# main.net
KiCad netlist of a schematic drawn in Altium Designer
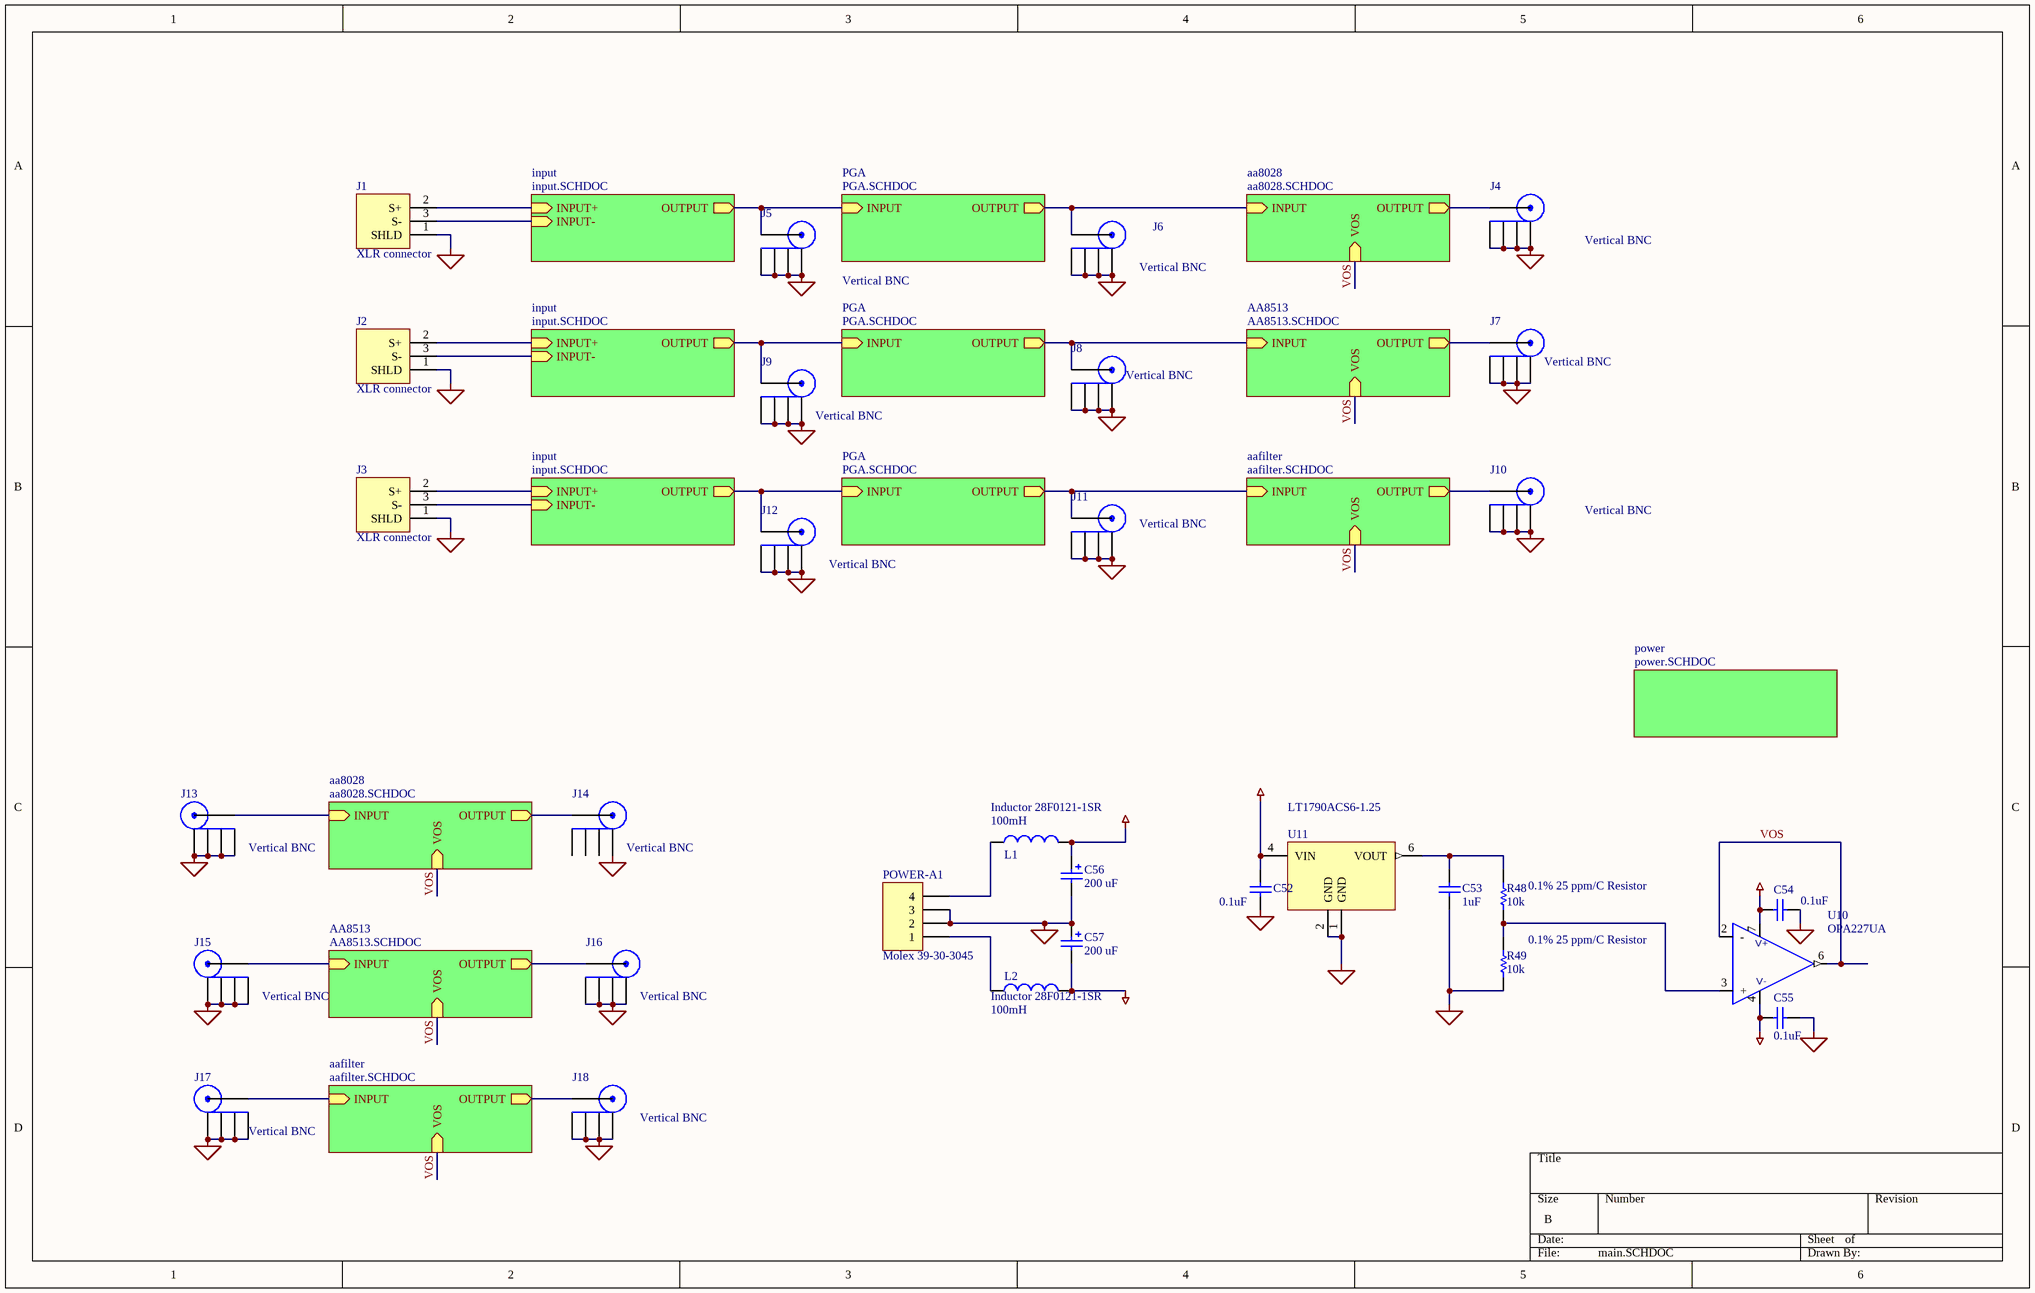
[diagram p0: main.SCHDOC]

(export (version "E")
  (design (tool "Eeschema 10.0.6"))
  (components
    (comp (ref "C52")
      (value "Cap")
      (footprint "CC1608-0603")
      (description "Capacitor")
      (fields
        (field (name "MANUFACTURER") "Generic Components")
        (field (name "ALTIUM_VALUE") "0.1uF")
        (field (name "PUBLISHER") "Altium Limited")
      )
      (libsource (lib "Miscellaneous Devices") (part "Cap"))
    )
    (comp (ref "C53")
      (value "Cap")
      (footprint "CC1608-0603")
      (description "Capacitor")
      (fields
        (field (name "MANUFACTURER") "Generic Components")
        (field (name "ALTIUM_VALUE") "1uF")
        (field (name "PUBLISHER") "Altium Limited")
      )
      (libsource (lib "Miscellaneous Devices") (part "Cap"))
    )
    (comp (ref "C54")
      (value "Cap")
      (footprint "CC1608-0603")
      (description "Capacitor")
      (fields
        (field (name "MANUFACTURER") "Generic Components")
        (field (name "ALTIUM_VALUE") "0.1uF")
        (field (name "PUBLISHER") "Altium Limited")
      )
      (libsource (lib "Miscellaneous Devices") (part "Cap"))
    )
    (comp (ref "C55")
      (value "Cap")
      (footprint "CC1608-0603")
      (description "Capacitor")
      (fields
        (field (name "MANUFACTURER") "Generic Components")
        (field (name "ALTIUM_VALUE") "0.1uF")
        (field (name "PUBLISHER") "Altium Limited")
      )
      (libsource (lib "Miscellaneous Devices") (part "Cap"))
    )
    (comp (ref "C56")
      (value "200 uF")
      (footprint "PanasonicE")
      (description "Polarized Capacitor (Surface Mount)")
      (fields (field (name "MANUFACTURER") "Generic Components") (field (name "PUBLISHER") "Altium Limited"))
      (libsource (lib "Miscellaneous Devices") (part "Cap Pol3"))
    )
    (comp (ref "C57")
      (value "200 uF")
      (footprint "PanasonicE")
      (description "Polarized Capacitor (Surface Mount)")
      (fields (field (name "MANUFACTURER") "Generic Components") (field (name "PUBLISHER") "Altium Limited"))
      (libsource (lib "Miscellaneous Devices") (part "Cap Pol3"))
    )
    (comp (ref "J1")
      (value "XLR connector")
      (footprint "NC3FAH-0")
      (description "XLR balanced connector, standard")
      (libsource (lib "My devices") (part "XLR"))
    )
    (comp (ref "J2")
      (value "XLR connector")
      (footprint "NC3FAH-0")
      (description "XLR balanced connector, standard")
      (libsource (lib "My devices") (part "XLR"))
    )
    (comp (ref "J3")
      (value "XLR connector")
      (footprint "NC3FAH-0")
      (description "XLR balanced connector, standard")
      (libsource (lib "My devices") (part "XLR"))
    )
    (comp (ref "J4")
      (value "Vertical BNC")
      (footprint "Vertical BNC 227699-1")
      (description "Vertical BNC with correct grounding pin behavior")
      (libsource (lib "My devices") (part "VERTBNC"))
    )
    (comp (ref "J5")
      (value "Vertical BNC")
      (footprint "Vertical BNC 227699-1")
      (description "Vertical BNC with correct grounding pin behavior")
      (libsource (lib "My devices") (part "VERTBNC"))
    )
    (comp (ref "J6")
      (value "Vertical BNC")
      (footprint "Vertical BNC 227699-1")
      (description "Vertical BNC with correct grounding pin behavior")
      (libsource (lib "My devices") (part "VERTBNC"))
    )
    (comp (ref "J7")
      (value "Vertical BNC")
      (footprint "Vertical BNC 227699-1")
      (description "Vertical BNC with correct grounding pin behavior")
      (libsource (lib "My devices") (part "VERTBNC"))
    )
    (comp (ref "J8")
      (value "Vertical BNC")
      (footprint "Vertical BNC 227699-1")
      (description "Vertical BNC with correct grounding pin behavior")
      (libsource (lib "My devices") (part "VERTBNC"))
    )
    (comp (ref "J9")
      (value "Vertical BNC")
      (footprint "Vertical BNC 227699-1")
      (description "Vertical BNC with correct grounding pin behavior")
      (libsource (lib "My devices") (part "VERTBNC"))
    )
    (comp (ref "J10")
      (value "Vertical BNC")
      (footprint "Vertical BNC 227699-1")
      (description "Vertical BNC with correct grounding pin behavior")
      (libsource (lib "My devices") (part "VERTBNC"))
    )
    (comp (ref "J11")
      (value "Vertical BNC")
      (footprint "Vertical BNC 227699-1")
      (description "Vertical BNC with correct grounding pin behavior")
      (libsource (lib "My devices") (part "VERTBNC"))
    )
    (comp (ref "J12")
      (value "Vertical BNC")
      (footprint "Vertical BNC 227699-1")
      (description "Vertical BNC with correct grounding pin behavior")
      (libsource (lib "My devices") (part "VERTBNC"))
    )
    (comp (ref "J13")
      (value "Vertical BNC")
      (footprint "Vertical BNC 227699-1")
      (description "Vertical BNC with correct grounding pin behavior")
      (libsource (lib "My devices") (part "VERTBNC"))
    )
    (comp (ref "J14")
      (value "Vertical BNC")
      (footprint "Vertical BNC 227699-1")
      (description "Vertical BNC with correct grounding pin behavior")
      (libsource (lib "My devices") (part "VERTBNC"))
    )
    (comp (ref "J15")
      (value "Vertical BNC")
      (footprint "Vertical BNC 227699-1")
      (description "Vertical BNC with correct grounding pin behavior")
      (libsource (lib "My devices") (part "VERTBNC"))
    )
    (comp (ref "J16")
      (value "Vertical BNC")
      (footprint "Vertical BNC 227699-1")
      (description "Vertical BNC with correct grounding pin behavior")
      (libsource (lib "My devices") (part "VERTBNC"))
    )
    (comp (ref "J17")
      (value "Vertical BNC")
      (footprint "Vertical BNC 227699-1")
      (description "Vertical BNC with correct grounding pin behavior")
      (libsource (lib "My devices") (part "VERTBNC"))
    )
    (comp (ref "J18")
      (value "Vertical BNC")
      (footprint "Vertical BNC 227699-1")
      (description "Vertical BNC with correct grounding pin behavior")
      (libsource (lib "My devices") (part "VERTBNC"))
    )
    (comp (ref "L1")
      (value "Inductor 28F0121-1SR")
      (footprint "STEWARD_1SR")
      (description "Inductor")
      (fields
        (field (name "MANUFACTURER") "Generic Components")
        (field (name "ALTIUM_VALUE") "100mH")
        (field (name "PUBLISHER") "Altium Limited")
      )
      (libsource (lib "Miscellaneous Devices") (part "Inductor"))
    )
    (comp (ref "L2")
      (value "Inductor 28F0121-1SR")
      (footprint "STEWARD_1SR")
      (description "Inductor")
      (fields
        (field (name "MANUFACTURER") "Generic Components")
        (field (name "ALTIUM_VALUE") "100mH")
        (field (name "PUBLISHER") "Altium Limited")
      )
      (libsource (lib "Miscellaneous Devices") (part "Inductor"))
    )
    (comp (ref "POWER-A1")
      (value "Molex 39-30-3045")
      (footprint "MJ4RTHR")
      (description "Header, 4-Pin")
      (fields (field (name "MANUFACTURER") "Generic Components") (field (name "PUBLISHER") "Altium Limited"))
      (libsource (lib "Miscellaneous Connectors") (part "Header 4"))
    )
    (comp (ref "R48")
      (value "0.1% 25 ppm/C Resistor")
      (footprint "C3216-1206")
      (description "Resistor")
      (fields
        (field (name "MANUFACTURER") "Generic Components")
        (field (name "ALTIUM_VALUE") "10k")
        (field (name "PUBLISHER") "Altium Limited")
      )
      (libsource (lib "Miscellaneous Devices") (part "Res1"))
    )
    (comp (ref "R49")
      (value "0.1% 25 ppm/C Resistor")
      (footprint "C3216-1206")
      (description "Resistor")
      (fields
        (field (name "MANUFACTURER") "Generic Components")
        (field (name "ALTIUM_VALUE") "10k")
        (field (name "PUBLISHER") "Altium Limited")
      )
      (libsource (lib "Miscellaneous Devices") (part "Res1"))
    )
    (comp (ref "U10")
      (value "OPA227UA")
      (footprint "SO-G8/D5.1")
      (libsource (lib "My devices") (part "OPA227UA"))
    )
    (comp (ref "U11")
      (value "LT1790ACS6-1.25")
      (footprint "LTI SOT-23 ThinSOT")
      (libsource (lib "My devices") (part "LT1790"))
    )
  )
  (nets
    (net (code "1") (name "/INPUT") (class "Default")
      (node (ref "J17") (pin "1") (pinfunction "PIN_1") (pintype "passive"))
    )
    (net (code "2") (name "/INPUT+") (class "Default")
      (node (ref "J3") (pin "2") (pinfunction "S+_2") (pintype "passive"))
    )
    (net (code "3") (name "/INPUT+_1") (class "Default")
      (node (ref "J1") (pin "2") (pinfunction "S+_2") (pintype "passive"))
    )
    (net (code "4") (name "/INPUT+_2") (class "Default")
      (node (ref "J2") (pin "2") (pinfunction "S+_2") (pintype "passive"))
    )
    (net (code "5") (name "/INPUT-") (class "Default")
      (node (ref "J2") (pin "3") (pinfunction "S-_3") (pintype "passive"))
    )
    (net (code "6") (name "/INPUT-_1") (class "Default")
      (node (ref "J1") (pin "3") (pinfunction "S-_3") (pintype "passive"))
    )
    (net (code "7") (name "/INPUT-_2") (class "Default")
      (node (ref "J3") (pin "3") (pinfunction "S-_3") (pintype "passive"))
    )
    (net (code "8") (name "/INPUT_1") (class "Default")
      (node (ref "J15") (pin "1") (pinfunction "PIN_1") (pintype "passive"))
    )
    (net (code "9") (name "/INPUT_2") (class "Default")
      (node (ref "J13") (pin "1") (pinfunction "PIN_1") (pintype "passive"))
    )
    (net (code "10") (name "/OUTPUT") (class "Default")
      (node (ref "J7") (pin "1") (pinfunction "PIN_1") (pintype "passive"))
    )
    (net (code "11") (name "/OUTPUT_1") (class "Default")
      (node (ref "J18") (pin "1") (pinfunction "PIN_1") (pintype "passive"))
    )
    (net (code "12") (name "/OUTPUT_2") (class "Default")
      (node (ref "J14") (pin "1") (pinfunction "PIN_1") (pintype "passive"))
    )
    (net (code "13") (name "/OUTPUT_3") (class "Default")
      (node (ref "J16") (pin "1") (pinfunction "PIN_1") (pintype "passive"))
    )
    (net (code "14") (name "/OUTPUT_4") (class "Default")
      (node (ref "J5") (pin "1") (pinfunction "PIN_1") (pintype "passive"))
    )
    (net (code "15") (name "/OUTPUT_5") (class "Default")
      (node (ref "J9") (pin "1") (pinfunction "PIN_1") (pintype "passive"))
    )
    (net (code "16") (name "/OUTPUT_6") (class "Default")
      (node (ref "J12") (pin "1") (pinfunction "PIN_1") (pintype "passive"))
    )
    (net (code "17") (name "/OUTPUT_7") (class "Default")
      (node (ref "J6") (pin "1") (pinfunction "PIN_1") (pintype "passive"))
    )
    (net (code "18") (name "/OUTPUT_8") (class "Default")
      (node (ref "J11") (pin "1") (pinfunction "PIN_1") (pintype "passive"))
    )
    (net (code "19") (name "/OUTPUT_9") (class "Default")
      (node (ref "J8") (pin "1") (pinfunction "PIN_1") (pintype "passive"))
    )
    (net (code "20") (name "/OUTPUT_10") (class "Default")
      (node (ref "J10") (pin "1") (pinfunction "PIN_1") (pintype "passive"))
    )
    (net (code "21") (name "/OUTPUT_11") (class "Default")
      (node (ref "J4") (pin "1") (pinfunction "PIN_1") (pintype "passive"))
    )
    (net (code "22") (name "/VOS") (class "Default")
      (node (ref "U10") (pin "2") (pinfunction "-_2") (pintype "passive"))
      (node (ref "U10") (pin "6") (pinfunction "Vout_6") (pintype "output"))
    )
    (net (code "23") (name "AVDD") (class "Default")
      (node (ref "C52") (pin "1") (pinfunction "1_1") (pintype "passive"))
      (node (ref "C54") (pin "2") (pinfunction "2_2") (pintype "passive"))
      (node (ref "C56") (pin "1") (pinfunction "1_1") (pintype "passive"))
      (node (ref "L1") (pin "2") (pinfunction "2_2") (pintype "passive"))
      (node (ref "U10") (pin "7") (pinfunction "V+_7") (pintype "power_in"))
      (node (ref "U11") (pin "4") (pinfunction "VIN_4") (pintype "power_in"))
    )
    (net (code "24") (name "AVSS") (class "Default")
      (node (ref "C55") (pin "2") (pinfunction "2_2") (pintype "passive"))
      (node (ref "C57") (pin "2") (pinfunction "2_2") (pintype "passive"))
      (node (ref "L2") (pin "2") (pinfunction "2_2") (pintype "passive"))
      (node (ref "U10") (pin "4") (pinfunction "V-_4") (pintype "power_in"))
    )
    (net (code "25") (name "GND") (class "Default")
      (node (ref "C52") (pin "2") (pinfunction "2_2") (pintype "passive"))
      (node (ref "C53") (pin "2") (pinfunction "2_2") (pintype "passive"))
      (node (ref "C54") (pin "1") (pinfunction "1_1") (pintype "passive"))
      (node (ref "C55") (pin "1") (pinfunction "1_1") (pintype "passive"))
      (node (ref "C56") (pin "2") (pinfunction "2_2") (pintype "passive"))
      (node (ref "C57") (pin "1") (pinfunction "1_1") (pintype "passive"))
      (node (ref "J1") (pin "1") (pinfunction "SHLD_1") (pintype "passive"))
      (node (ref "J10") (pin "2") (pinfunction "SHLD_2") (pintype "passive"))
      (node (ref "J10") (pin "3") (pinfunction "SHLD_3") (pintype "passive"))
      (node (ref "J10") (pin "4") (pinfunction "SHLD_4") (pintype "passive"))
      (node (ref "J10") (pin "5") (pinfunction "SHLD_5") (pintype "passive"))
      (node (ref "J11") (pin "2") (pinfunction "SHLD_2") (pintype "passive"))
      (node (ref "J11") (pin "3") (pinfunction "SHLD_3") (pintype "passive"))
      (node (ref "J11") (pin "4") (pinfunction "SHLD_4") (pintype "passive"))
      (node (ref "J11") (pin "5") (pinfunction "SHLD_5") (pintype "passive"))
      (node (ref "J12") (pin "2") (pinfunction "SHLD_2") (pintype "passive"))
      (node (ref "J12") (pin "3") (pinfunction "SHLD_3") (pintype "passive"))
      (node (ref "J12") (pin "4") (pinfunction "SHLD_4") (pintype "passive"))
      (node (ref "J12") (pin "5") (pinfunction "SHLD_5") (pintype "passive"))
      (node (ref "J13") (pin "2") (pinfunction "SHLD_2") (pintype "passive"))
      (node (ref "J13") (pin "3") (pinfunction "SHLD_3") (pintype "passive"))
      (node (ref "J13") (pin "4") (pinfunction "SHLD_4") (pintype "passive"))
      (node (ref "J13") (pin "5") (pinfunction "SHLD_5") (pintype "passive"))
      (node (ref "J14") (pin "2") (pinfunction "SHLD_2") (pintype "passive"))
      (node (ref "J15") (pin "2") (pinfunction "SHLD_2") (pintype "passive"))
      (node (ref "J15") (pin "3") (pinfunction "SHLD_3") (pintype "passive"))
      (node (ref "J15") (pin "4") (pinfunction "SHLD_4") (pintype "passive"))
      (node (ref "J15") (pin "5") (pinfunction "SHLD_5") (pintype "passive"))
      (node (ref "J16") (pin "2") (pinfunction "SHLD_2") (pintype "passive"))
      (node (ref "J16") (pin "3") (pinfunction "SHLD_3") (pintype "passive"))
      (node (ref "J16") (pin "4") (pinfunction "SHLD_4") (pintype "passive"))
      (node (ref "J16") (pin "5") (pinfunction "SHLD_5") (pintype "passive"))
      (node (ref "J17") (pin "2") (pinfunction "SHLD_2") (pintype "passive"))
      (node (ref "J17") (pin "3") (pinfunction "SHLD_3") (pintype "passive"))
      (node (ref "J17") (pin "4") (pinfunction "SHLD_4") (pintype "passive"))
      (node (ref "J17") (pin "5") (pinfunction "SHLD_5") (pintype "passive"))
      (node (ref "J18") (pin "2") (pinfunction "SHLD_2") (pintype "passive"))
      (node (ref "J18") (pin "3") (pinfunction "SHLD_3") (pintype "passive"))
      (node (ref "J18") (pin "4") (pinfunction "SHLD_4") (pintype "passive"))
      (node (ref "J18") (pin "5") (pinfunction "SHLD_5") (pintype "passive"))
      (node (ref "J2") (pin "1") (pinfunction "SHLD_1") (pintype "passive"))
      (node (ref "J3") (pin "1") (pinfunction "SHLD_1") (pintype "passive"))
      (node (ref "J4") (pin "2") (pinfunction "SHLD_2") (pintype "passive"))
      (node (ref "J4") (pin "3") (pinfunction "SHLD_3") (pintype "passive"))
      (node (ref "J4") (pin "4") (pinfunction "SHLD_4") (pintype "passive"))
      (node (ref "J4") (pin "5") (pinfunction "SHLD_5") (pintype "passive"))
      (node (ref "J5") (pin "2") (pinfunction "SHLD_2") (pintype "passive"))
      (node (ref "J5") (pin "3") (pinfunction "SHLD_3") (pintype "passive"))
      (node (ref "J5") (pin "4") (pinfunction "SHLD_4") (pintype "passive"))
      (node (ref "J5") (pin "5") (pinfunction "SHLD_5") (pintype "passive"))
      (node (ref "J6") (pin "2") (pinfunction "SHLD_2") (pintype "passive"))
      (node (ref "J6") (pin "3") (pinfunction "SHLD_3") (pintype "passive"))
      (node (ref "J6") (pin "4") (pinfunction "SHLD_4") (pintype "passive"))
      (node (ref "J6") (pin "5") (pinfunction "SHLD_5") (pintype "passive"))
      (node (ref "J7") (pin "2") (pinfunction "SHLD_2") (pintype "passive"))
      (node (ref "J7") (pin "3") (pinfunction "SHLD_3") (pintype "passive"))
      (node (ref "J7") (pin "4") (pinfunction "SHLD_4") (pintype "passive"))
      (node (ref "J7") (pin "5") (pinfunction "SHLD_5") (pintype "passive"))
      (node (ref "J8") (pin "2") (pinfunction "SHLD_2") (pintype "passive"))
      (node (ref "J8") (pin "3") (pinfunction "SHLD_3") (pintype "passive"))
      (node (ref "J8") (pin "4") (pinfunction "SHLD_4") (pintype "passive"))
      (node (ref "J8") (pin "5") (pinfunction "SHLD_5") (pintype "passive"))
      (node (ref "J9") (pin "2") (pinfunction "SHLD_2") (pintype "passive"))
      (node (ref "J9") (pin "3") (pinfunction "SHLD_3") (pintype "passive"))
      (node (ref "J9") (pin "4") (pinfunction "SHLD_4") (pintype "passive"))
      (node (ref "J9") (pin "5") (pinfunction "SHLD_5") (pintype "passive"))
      (node (ref "POWER-A1") (pin "2") (pinfunction "2_2") (pintype "passive"))
      (node (ref "POWER-A1") (pin "3") (pinfunction "3_3") (pintype "passive"))
      (node (ref "R49") (pin "1") (pinfunction "1_1") (pintype "passive"))
      (node (ref "U11") (pin "1") (pinfunction "GND_1") (pintype "power_in"))
      (node (ref "U11") (pin "2") (pinfunction "GND_2") (pintype "power_in"))
    )
    (net (code "26") (name "Net-(L1-Pad1)") (class "Default")
      (node (ref "L1") (pin "1") (pinfunction "1_1") (pintype "passive"))
      (node (ref "POWER-A1") (pin "4") (pinfunction "4_4") (pintype "passive"))
    )
    (net (code "27") (name "Net-(L2-Pad1)") (class "Default")
      (node (ref "L2") (pin "1") (pinfunction "1_1") (pintype "passive"))
      (node (ref "POWER-A1") (pin "1") (pinfunction "1_1") (pintype "passive"))
    )
    (net (code "28") (name "Net-(U10-+)") (class "Default")
      (node (ref "R48") (pin "1") (pinfunction "1_1") (pintype "passive"))
      (node (ref "R49") (pin "2") (pinfunction "2_2") (pintype "passive"))
      (node (ref "U10") (pin "3") (pinfunction "+_3") (pintype "passive"))
    )
    (net (code "29") (name "Net-(U11-VOUT)") (class "Default")
      (node (ref "C53") (pin "1") (pinfunction "1_1") (pintype "passive"))
      (node (ref "R48") (pin "2") (pinfunction "2_2") (pintype "passive"))
      (node (ref "U11") (pin "6") (pinfunction "VOUT_6") (pintype "output"))
    )
    (net (code "30") (name "unconnected-(J14-SHLD-Pad3)") (class "Default")
      (node (ref "J14") (pin "3") (pinfunction "SHLD_3") (pintype "passive"))
    )
    (net (code "31") (name "unconnected-(J14-SHLD-Pad4)") (class "Default")
      (node (ref "J14") (pin "4") (pinfunction "SHLD_4") (pintype "passive"))
    )
    (net (code "32") (name "unconnected-(J14-SHLD-Pad5)") (class "Default")
      (node (ref "J14") (pin "5") (pinfunction "SHLD_5") (pintype "passive"))
    )
  )
)
